# SignalBoard.net
KiCad netlist of a schematic drawn in Altium Designer
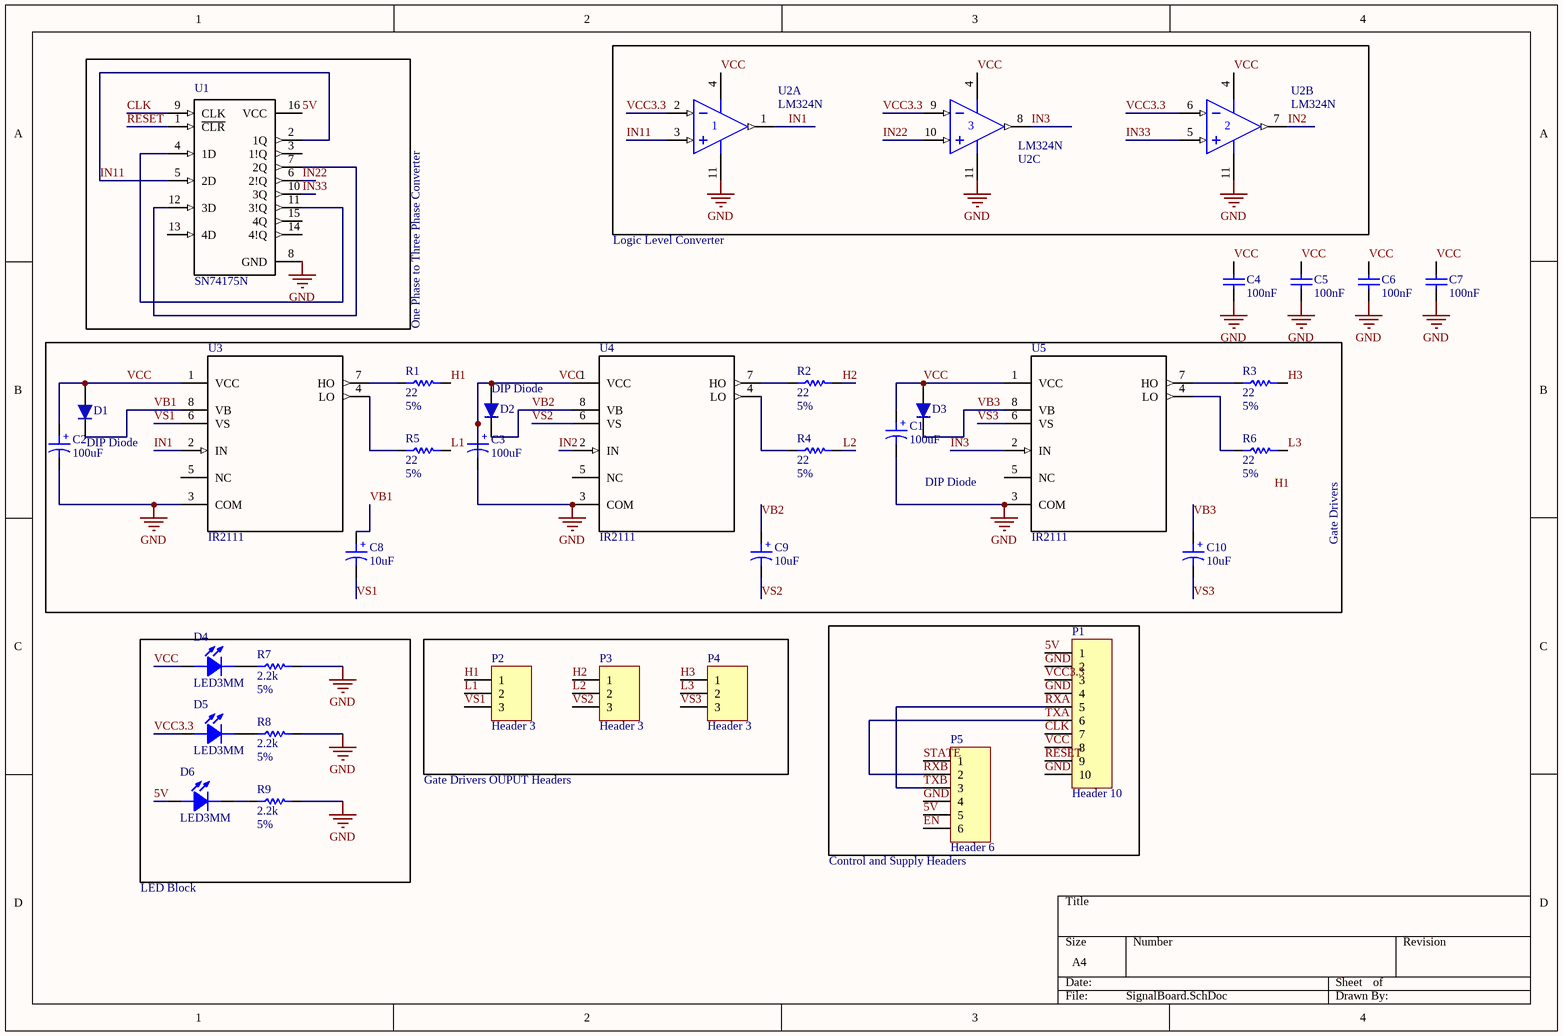
[diagram p0: SignalBoard.SchDoc]

(export (version "E")
  (design (tool "Eeschema 10.0.6"))
  (components
    (comp (ref "C1")
      (value "100uF")
      (footprint "Cap electrolitic radial 6.3x12-2.5")
      (description "Cap electrolitic radial")
      (fields (field (name "DESIGNER") "Abbas Basereh"))
      (libsource (lib "Altium") (part "Cap ELECTROLITIC TOTAL SIZE"))
    )
    (comp (ref "C2")
      (value "100uF")
      (footprint "Cap electrolitic radial 6.3x12-2.5")
      (description "Cap electrolitic radial")
      (fields (field (name "DESIGNER") "Abbas Basereh"))
      (libsource (lib "Altium") (part "Cap ELECTROLITIC TOTAL SIZE"))
    )
    (comp (ref "C3")
      (value "100uF")
      (footprint "Cap electrolitic radial 6.3x12-2.5")
      (description "Cap electrolitic radial")
      (fields (field (name "DESIGNER") "Abbas Basereh"))
      (libsource (lib "Altium") (part "Cap ELECTROLITIC TOTAL SIZE"))
    )
    (comp (ref "C4")
      (value "100nF")
      (footprint "Cap-100nF")
      (description "CAP Ceramic Total")
      (fields (field (name "DESIGNER") "Ali Hafizi"))
      (libsource (lib "Altium") (part "CAP CERAMIC TOTAL SIZE"))
    )
    (comp (ref "C5")
      (value "100nF")
      (footprint "Cap-100nF")
      (description "CAP Ceramic Total")
      (fields (field (name "DESIGNER") "Ali Hafizi"))
      (libsource (lib "Altium") (part "CAP CERAMIC TOTAL SIZE"))
    )
    (comp (ref "C6")
      (value "100nF")
      (footprint "Cap-100nF")
      (description "CAP Ceramic Total")
      (fields (field (name "DESIGNER") "Ali Hafizi"))
      (libsource (lib "Altium") (part "CAP CERAMIC TOTAL SIZE"))
    )
    (comp (ref "C7")
      (value "100nF")
      (footprint "Cap-100nF")
      (description "CAP Ceramic Total")
      (fields (field (name "DESIGNER") "Ali Hafizi"))
      (libsource (lib "Altium") (part "CAP CERAMIC TOTAL SIZE"))
    )
    (comp (ref "C8")
      (value "10uF")
      (footprint "Cap electrolitic radial 5x11-2")
      (description "Cap electrolitic radial")
      (fields (field (name "DESIGNER") "Abbas Basereh"))
      (libsource (lib "Altium") (part "Cap ELECTROLITIC TOTAL SIZE"))
    )
    (comp (ref "C9")
      (value "10uF")
      (footprint "Cap electrolitic radial 5x11-2")
      (description "Cap electrolitic radial")
      (fields (field (name "DESIGNER") "Abbas Basereh"))
      (libsource (lib "Altium") (part "Cap ELECTROLITIC TOTAL SIZE"))
    )
    (comp (ref "C10")
      (value "10uF")
      (footprint "Cap electrolitic radial 5x11-2")
      (description "Cap electrolitic radial")
      (fields (field (name "DESIGNER") "Abbas Basereh"))
      (libsource (lib "Altium") (part "Cap ELECTROLITIC TOTAL SIZE"))
    )
    (comp (ref "D1")
      (value "DIP Diode")
      (footprint "Diode 1n4007")
      (description "Diode DIP Package")
      (fields (field (name "PUBLISHER") "Altium Limited"))
      (libsource (lib "Altium") (part "Diode DIP Package"))
    )
    (comp (ref "D2")
      (value "DIP Diode")
      (footprint "Diode 1n4007")
      (description "Diode DIP Package")
      (fields (field (name "PUBLISHER") "Altium Limited"))
      (libsource (lib "Altium") (part "Diode DIP Package"))
    )
    (comp (ref "D3")
      (value "DIP Diode")
      (footprint "Diode 1n4007")
      (description "Diode DIP Package")
      (fields (field (name "PUBLISHER") "Altium Limited"))
      (libsource (lib "Altium") (part "Diode DIP Package"))
    )
    (comp (ref "D4")
      (value "LED3MM")
      (footprint "LED3mm_GRN")
      (description "Light Emitting Diode")
      (fields (field (name "DESIGNER") "Ali Hafizi"))
      (libsource (lib "Altium") (part "LED 3MM"))
    )
    (comp (ref "D5")
      (value "LED3MM")
      (footprint "LED3mm_GRN")
      (description "Light Emitting Diode")
      (fields (field (name "DESIGNER") "Ali Hafizi"))
      (libsource (lib "Altium") (part "LED 3MM"))
    )
    (comp (ref "D6")
      (value "LED3MM")
      (footprint "LED3mm_GRN")
      (description "Light Emitting Diode")
      (fields (field (name "DESIGNER") "Ali Hafizi"))
      (libsource (lib "Altium") (part "LED 3MM"))
    )
    (comp (ref "P1")
      (value "Header 10")
      (footprint "HDR1X10")
      (description "Header, 10-Pin")
      (fields (field (name "PUBLISHER") "Altium Limited"))
      (libsource (lib "Miscellaneous Connectors") (part "Header 10"))
    )
    (comp (ref "P2")
      (value "Header 3")
      (footprint "HDR1X3")
      (description "Header, 3-Pin")
      (fields (field (name "PUBLISHER") "Altium Limited"))
      (libsource (lib "Altium") (part "Header 3"))
    )
    (comp (ref "P3")
      (value "Header 3")
      (footprint "HDR1X3")
      (description "Header, 3-Pin")
      (fields (field (name "PUBLISHER") "Altium Limited"))
      (libsource (lib "Altium") (part "Header 3"))
    )
    (comp (ref "P4")
      (value "Header 3")
      (footprint "HDR1X3")
      (description "Header, 3-Pin")
      (fields (field (name "PUBLISHER") "Altium Limited"))
      (libsource (lib "Altium") (part "Header 3"))
    )
    (comp (ref "P5")
      (value "Header 6")
      (footprint "HDR1X6")
      (description "Header, 6-Pin")
      (fields (field (name "PUBLISHER") "Altium Limited"))
      (libsource (lib "Miscellaneous Connectors") (part "Header 6"))
    )
    (comp (ref "R1")
      (value "22")
      (footprint "Res-(1/4)")
      (description "Resistor")
      (fields (field (name "TOLERANCE") "5%"))
      (libsource (lib "My_Library") (part "Resistor"))
    )
    (comp (ref "R2")
      (value "22")
      (footprint "Res-(1/4)")
      (description "Resistor")
      (fields (field (name "TOLERANCE") "5%"))
      (libsource (lib "My_Library") (part "Resistor"))
    )
    (comp (ref "R3")
      (value "22")
      (footprint "Res-(1/4)")
      (description "Resistor")
      (fields (field (name "TOLERANCE") "5%"))
      (libsource (lib "My_Library") (part "Resistor"))
    )
    (comp (ref "R4")
      (value "22")
      (footprint "Res-(1/4)")
      (description "Resistor")
      (fields (field (name "TOLERANCE") "5%"))
      (libsource (lib "My_Library") (part "Resistor"))
    )
    (comp (ref "R5")
      (value "22")
      (footprint "Res-(1/4)")
      (description "Resistor")
      (fields (field (name "TOLERANCE") "5%"))
      (libsource (lib "My_Library") (part "Resistor"))
    )
    (comp (ref "R6")
      (value "22")
      (footprint "Res-(1/4)")
      (description "Resistor")
      (fields (field (name "TOLERANCE") "5%"))
      (libsource (lib "My_Library") (part "Resistor"))
    )
    (comp (ref "R7")
      (value "2.2k")
      (footprint "Res-(1/4)")
      (description "Resistor")
      (fields (field (name "TOLERANCE") "5%"))
      (libsource (lib "My_Library") (part "Resistor"))
    )
    (comp (ref "R8")
      (value "2.2k")
      (footprint "Res-(1/4)")
      (description "Resistor")
      (fields (field (name "TOLERANCE") "5%"))
      (libsource (lib "My_Library") (part "Resistor"))
    )
    (comp (ref "R9")
      (value "2.2k")
      (footprint "Res-(1/4)")
      (description "Resistor")
      (fields (field (name "TOLERANCE") "5%"))
      (libsource (lib "My_Library") (part "Resistor"))
    )
    (comp (ref "U1")
      (value "SN74175N")
      (footprint "*DIP762W46P254L2134H508Q16")
      (description "Quadruple D-Type Flip-Flops With Clear 16-PDIP 0 to 70")
      (fields (field (name "MF") "Texas Instruments"))
      (libsource (lib "SN74175N") (part "SN74175N"))
    )
    (comp (ref "U2")
      (value "LM324N")
      (footprint "646-06")
      (description "Quad Low-Power Operational Amplifier")
      (fields (field (name "PUBLISHER") "Altium Limited"))
      (libsource (lib "Devices") (part "LM324N"))
    )
    (comp (ref "U3")
      (value "IR2111")
      (footprint "*DIP254P762X533-8")
      (description "Half Bridge Driver, Fixed 650ns Deadtime in a 8-Lead package")
      (fields (field (name "MF") "Infineon"))
      (libsource (lib "IR2111") (part "IR2111"))
    )
    (comp (ref "U4")
      (value "IR2111")
      (footprint "*DIP254P762X533-8")
      (description "Half Bridge Driver, Fixed 650ns Deadtime in a 8-Lead package")
      (fields (field (name "MF") "Infineon"))
      (libsource (lib "IR2111") (part "IR2111"))
    )
    (comp (ref "U5")
      (value "IR2111")
      (footprint "*DIP254P762X533-8")
      (description "Half Bridge Driver, Fixed 650ns Deadtime in a 8-Lead package")
      (fields (field (name "MF") "Infineon"))
      (libsource (lib "IR2111") (part "IR2111"))
    )
  )
  (nets
    (net (code "1") (name "/5V") (class "Default")
      (node (ref "D6") (pin "1") (pinfunction "ANODE_1") (pintype "passive"))
      (node (ref "P1") (pin "1") (pinfunction "1_1") (pintype "passive"))
      (node (ref "P5") (pin "5") (pinfunction "5_5") (pintype "passive"))
      (node (ref "U1") (pin "16") (pinfunction "VCC_16") (pintype "power_in"))
    )
    (net (code "2") (name "/CLK") (class "Default")
      (node (ref "P1") (pin "7") (pinfunction "7_7") (pintype "passive"))
      (node (ref "U1") (pin "9") (pinfunction "CLK_9") (pintype "input"))
    )
    (net (code "3") (name "/EN") (class "Default")
      (node (ref "P5") (pin "6") (pinfunction "6_6") (pintype "passive"))
    )
    (net (code "4") (name "/H1") (class "Default")
      (node (ref "P2") (pin "1") (pinfunction "1_1") (pintype "passive"))
      (node (ref "R1") (pin "2") (pinfunction "2_2") (pintype "passive"))
    )
    (net (code "5") (name "/H2") (class "Default")
      (node (ref "P3") (pin "1") (pinfunction "1_1") (pintype "passive"))
      (node (ref "R2") (pin "2") (pinfunction "2_2") (pintype "passive"))
    )
    (net (code "6") (name "/H3") (class "Default")
      (node (ref "P4") (pin "1") (pinfunction "1_1") (pintype "passive"))
      (node (ref "R3") (pin "2") (pinfunction "2_2") (pintype "passive"))
    )
    (net (code "7") (name "/IN1") (class "Default")
      (node (ref "U2") (pin "1") (pinfunction "OUT_1") (pintype "output"))
      (node (ref "U3") (pin "2") (pinfunction "IN_2") (pintype "input"))
    )
    (net (code "8") (name "/IN2") (class "Default")
      (node (ref "U2") (pin "7") (pinfunction "OUT_7") (pintype "output"))
      (node (ref "U4") (pin "2") (pinfunction "IN_2") (pintype "input"))
    )
    (net (code "9") (name "/IN3") (class "Default")
      (node (ref "U2") (pin "8") (pinfunction "OUT_8") (pintype "output"))
      (node (ref "U5") (pin "2") (pinfunction "IN_2") (pintype "input"))
    )
    (net (code "10") (name "/IN11") (class "Default")
      (node (ref "U1") (pin "2") (pinfunction "1Q_2") (pintype "output"))
      (node (ref "U1") (pin "5") (pinfunction "2D_5") (pintype "input"))
      (node (ref "U2") (pin "3") (pinfunction "IN+_3") (pintype "input"))
    )
    (net (code "11") (name "/IN22") (class "Default")
      (node (ref "U1") (pin "6") (pinfunction "2!Q_6") (pintype "output"))
      (node (ref "U2") (pin "10") (pinfunction "IN+_10") (pintype "input"))
    )
    (net (code "12") (name "/IN33") (class "Default")
      (node (ref "U1") (pin "10") (pinfunction "3Q_10") (pintype "output"))
      (node (ref "U2") (pin "5") (pinfunction "IN+_5") (pintype "input"))
    )
    (net (code "13") (name "/L1") (class "Default")
      (node (ref "P2") (pin "2") (pinfunction "2_2") (pintype "passive"))
      (node (ref "R5") (pin "2") (pinfunction "2_2") (pintype "passive"))
    )
    (net (code "14") (name "/L2") (class "Default")
      (node (ref "P3") (pin "2") (pinfunction "2_2") (pintype "passive"))
      (node (ref "R4") (pin "2") (pinfunction "2_2") (pintype "passive"))
    )
    (net (code "15") (name "/L3") (class "Default")
      (node (ref "P4") (pin "2") (pinfunction "2_2") (pintype "passive"))
      (node (ref "R6") (pin "2") (pinfunction "2_2") (pintype "passive"))
    )
    (net (code "16") (name "/RESET") (class "Default")
      (node (ref "P1") (pin "9") (pinfunction "9_9") (pintype "passive"))
      (node (ref "U1") (pin "1") (pinfunction "~{CLR}_1") (pintype "input"))
    )
    (net (code "17") (name "/RXA") (class "Default")
      (node (ref "P1") (pin "5") (pinfunction "5_5") (pintype "passive"))
      (node (ref "P5") (pin "3") (pinfunction "3_3") (pintype "passive"))
    )
    (net (code "18") (name "/RXB") (class "Default")
      (node (ref "P1") (pin "6") (pinfunction "6_6") (pintype "passive"))
      (node (ref "P5") (pin "2") (pinfunction "2_2") (pintype "passive"))
    )
    (net (code "19") (name "/STATE") (class "Default")
      (node (ref "P5") (pin "1") (pinfunction "1_1") (pintype "passive"))
    )
    (net (code "20") (name "/VB1") (class "Default")
      (node (ref "C8") (pin "1") (pinfunction "1_1") (pintype "passive"))
      (node (ref "D1") (pin "2") (pintype "passive"))
      (node (ref "U3") (pin "8") (pinfunction "VB_8") (pintype "power_in"))
    )
    (net (code "21") (name "/VB2") (class "Default")
      (node (ref "C9") (pin "1") (pinfunction "1_1") (pintype "passive"))
      (node (ref "D2") (pin "2") (pintype "passive"))
      (node (ref "U4") (pin "8") (pinfunction "VB_8") (pintype "power_in"))
    )
    (net (code "22") (name "/VB3") (class "Default")
      (node (ref "C10") (pin "1") (pinfunction "1_1") (pintype "passive"))
      (node (ref "D3") (pin "2") (pintype "passive"))
      (node (ref "U5") (pin "8") (pinfunction "VB_8") (pintype "power_in"))
    )
    (net (code "23") (name "/VCC") (class "Default")
      (node (ref "C1") (pin "1") (pinfunction "1_1") (pintype "passive"))
      (node (ref "C2") (pin "1") (pinfunction "1_1") (pintype "passive"))
      (node (ref "C3") (pin "1") (pinfunction "1_1") (pintype "passive"))
      (node (ref "C4") (pin "2") (pinfunction "2_2") (pintype "passive"))
      (node (ref "C5") (pin "2") (pinfunction "2_2") (pintype "passive"))
      (node (ref "C6") (pin "2") (pinfunction "2_2") (pintype "passive"))
      (node (ref "C7") (pin "2") (pinfunction "2_2") (pintype "passive"))
      (node (ref "D1") (pin "1") (pintype "passive"))
      (node (ref "D2") (pin "1") (pintype "passive"))
      (node (ref "D3") (pin "1") (pintype "passive"))
      (node (ref "D4") (pin "1") (pinfunction "ANODE_1") (pintype "passive"))
      (node (ref "P1") (pin "8") (pinfunction "8_8") (pintype "passive"))
      (node (ref "U2") (pin "4") (pinfunction "V+_4") (pintype "power_in"))
      (node (ref "U3") (pin "1") (pinfunction "VCC_1") (pintype "power_in"))
      (node (ref "U4") (pin "1") (pinfunction "VCC_1") (pintype "power_in"))
      (node (ref "U5") (pin "1") (pinfunction "VCC_1") (pintype "power_in"))
    )
    (net (code "24") (name "/VCC3.3") (class "Default")
      (node (ref "D5") (pin "1") (pinfunction "ANODE_1") (pintype "passive"))
      (node (ref "P1") (pin "3") (pinfunction "3_3") (pintype "passive"))
      (node (ref "U2") (pin "2") (pinfunction "IN-_2") (pintype "input"))
      (node (ref "U2") (pin "6") (pinfunction "IN-_6") (pintype "input"))
      (node (ref "U2") (pin "9") (pinfunction "IN-_9") (pintype "input"))
    )
    (net (code "25") (name "/VS1") (class "Default")
      (node (ref "C8") (pin "2") (pinfunction "2_2") (pintype "passive"))
      (node (ref "P2") (pin "3") (pinfunction "3_3") (pintype "passive"))
      (node (ref "U3") (pin "6") (pinfunction "VS_6") (pintype "power_in"))
    )
    (net (code "26") (name "/VS2") (class "Default")
      (node (ref "C9") (pin "2") (pinfunction "2_2") (pintype "passive"))
      (node (ref "P3") (pin "3") (pinfunction "3_3") (pintype "passive"))
      (node (ref "U4") (pin "6") (pinfunction "VS_6") (pintype "power_in"))
    )
    (net (code "27") (name "/VS3") (class "Default")
      (node (ref "C10") (pin "2") (pinfunction "2_2") (pintype "passive"))
      (node (ref "P4") (pin "3") (pinfunction "3_3") (pintype "passive"))
      (node (ref "U5") (pin "6") (pinfunction "VS_6") (pintype "power_in"))
    )
    (net (code "28") (name "GND") (class "Default")
      (node (ref "C1") (pin "2") (pinfunction "2_2") (pintype "passive"))
      (node (ref "C2") (pin "2") (pinfunction "2_2") (pintype "passive"))
      (node (ref "C3") (pin "2") (pinfunction "2_2") (pintype "passive"))
      (node (ref "C4") (pin "1") (pinfunction "1_1") (pintype "passive"))
      (node (ref "C5") (pin "1") (pinfunction "1_1") (pintype "passive"))
      (node (ref "C6") (pin "1") (pinfunction "1_1") (pintype "passive"))
      (node (ref "C7") (pin "1") (pinfunction "1_1") (pintype "passive"))
      (node (ref "P1") (pin "10") (pinfunction "10_10") (pintype "passive"))
      (node (ref "P1") (pin "2") (pinfunction "2_2") (pintype "passive"))
      (node (ref "P1") (pin "4") (pinfunction "4_4") (pintype "passive"))
      (node (ref "P5") (pin "4") (pinfunction "4_4") (pintype "passive"))
      (node (ref "R7") (pin "2") (pinfunction "2_2") (pintype "passive"))
      (node (ref "R8") (pin "2") (pinfunction "2_2") (pintype "passive"))
      (node (ref "R9") (pin "2") (pinfunction "2_2") (pintype "passive"))
      (node (ref "U1") (pin "8") (pinfunction "GND_8") (pintype "passive"))
      (node (ref "U2") (pin "11") (pinfunction "V-_11") (pintype "power_in"))
      (node (ref "U3") (pin "3") (pinfunction "COM_3") (pintype "passive"))
      (node (ref "U4") (pin "3") (pinfunction "COM_3") (pintype "passive"))
      (node (ref "U5") (pin "3") (pinfunction "COM_3") (pintype "passive"))
    )
    (net (code "29") (name "Net-(D4-CATHODE)") (class "Default")
      (node (ref "D4") (pin "2") (pinfunction "CATHODE_2") (pintype "passive"))
      (node (ref "R7") (pin "1") (pinfunction "1_1") (pintype "passive"))
    )
    (net (code "30") (name "Net-(D5-CATHODE)") (class "Default")
      (node (ref "D5") (pin "2") (pinfunction "CATHODE_2") (pintype "passive"))
      (node (ref "R8") (pin "1") (pinfunction "1_1") (pintype "passive"))
    )
    (net (code "31") (name "Net-(D6-CATHODE)") (class "Default")
      (node (ref "D6") (pin "2") (pinfunction "CATHODE_2") (pintype "passive"))
      (node (ref "R9") (pin "1") (pinfunction "1_1") (pintype "passive"))
    )
    (net (code "32") (name "Net-(U1-1D)") (class "Default")
      (node (ref "U1") (pin "11") (pinfunction "3!Q_11") (pintype "output"))
      (node (ref "U1") (pin "4") (pinfunction "1D_4") (pintype "input"))
    )
    (net (code "33") (name "Net-(U1-2Q)") (class "Default")
      (node (ref "U1") (pin "12") (pinfunction "3D_12") (pintype "input"))
      (node (ref "U1") (pin "7") (pinfunction "2Q_7") (pintype "output"))
    )
    (net (code "34") (name "Net-(U3-HO)") (class "Default")
      (node (ref "R1") (pin "1") (pinfunction "1_1") (pintype "passive"))
      (node (ref "U3") (pin "7") (pinfunction "HO_7") (pintype "output"))
    )
    (net (code "35") (name "Net-(U3-LO)") (class "Default")
      (node (ref "R5") (pin "1") (pinfunction "1_1") (pintype "passive"))
      (node (ref "U3") (pin "4") (pinfunction "LO_4") (pintype "output"))
    )
    (net (code "36") (name "Net-(U4-HO)") (class "Default")
      (node (ref "R2") (pin "1") (pinfunction "1_1") (pintype "passive"))
      (node (ref "U4") (pin "7") (pinfunction "HO_7") (pintype "output"))
    )
    (net (code "37") (name "Net-(U4-LO)") (class "Default")
      (node (ref "R4") (pin "1") (pinfunction "1_1") (pintype "passive"))
      (node (ref "U4") (pin "4") (pinfunction "LO_4") (pintype "output"))
    )
    (net (code "38") (name "Net-(U5-HO)") (class "Default")
      (node (ref "R3") (pin "1") (pinfunction "1_1") (pintype "passive"))
      (node (ref "U5") (pin "7") (pinfunction "HO_7") (pintype "output"))
    )
    (net (code "39") (name "Net-(U5-LO)") (class "Default")
      (node (ref "R6") (pin "1") (pinfunction "1_1") (pintype "passive"))
      (node (ref "U5") (pin "4") (pinfunction "LO_4") (pintype "output"))
    )
    (net (code "40") (name "unconnected-(U1-1!Q-Pad3)") (class "Default")
      (node (ref "U1") (pin "3") (pinfunction "1!Q_3") (pintype "output"))
    )
    (net (code "41") (name "unconnected-(U1-4!Q-Pad14)") (class "Default")
      (node (ref "U1") (pin "14") (pinfunction "4!Q_14") (pintype "output"))
    )
    (net (code "42") (name "unconnected-(U1-4D-Pad13)") (class "Default")
      (node (ref "U1") (pin "13") (pinfunction "4D_13") (pintype "input"))
    )
    (net (code "43") (name "unconnected-(U1-4Q-Pad15)") (class "Default")
      (node (ref "U1") (pin "15") (pinfunction "4Q_15") (pintype "output"))
    )
    (net (code "44") (name "unconnected-(U3-NC-Pad5)") (class "Default")
      (node (ref "U3") (pin "5") (pinfunction "NC_5") (pintype "passive"))
    )
    (net (code "45") (name "unconnected-(U4-NC-Pad5)") (class "Default")
      (node (ref "U4") (pin "5") (pinfunction "NC_5") (pintype "passive"))
    )
    (net (code "46") (name "unconnected-(U5-NC-Pad5)") (class "Default")
      (node (ref "U5") (pin "5") (pinfunction "NC_5") (pintype "passive"))
    )
  )
)
